# WirelessLamp.net
KiCad netlist of a schematic drawn in Altium Designer
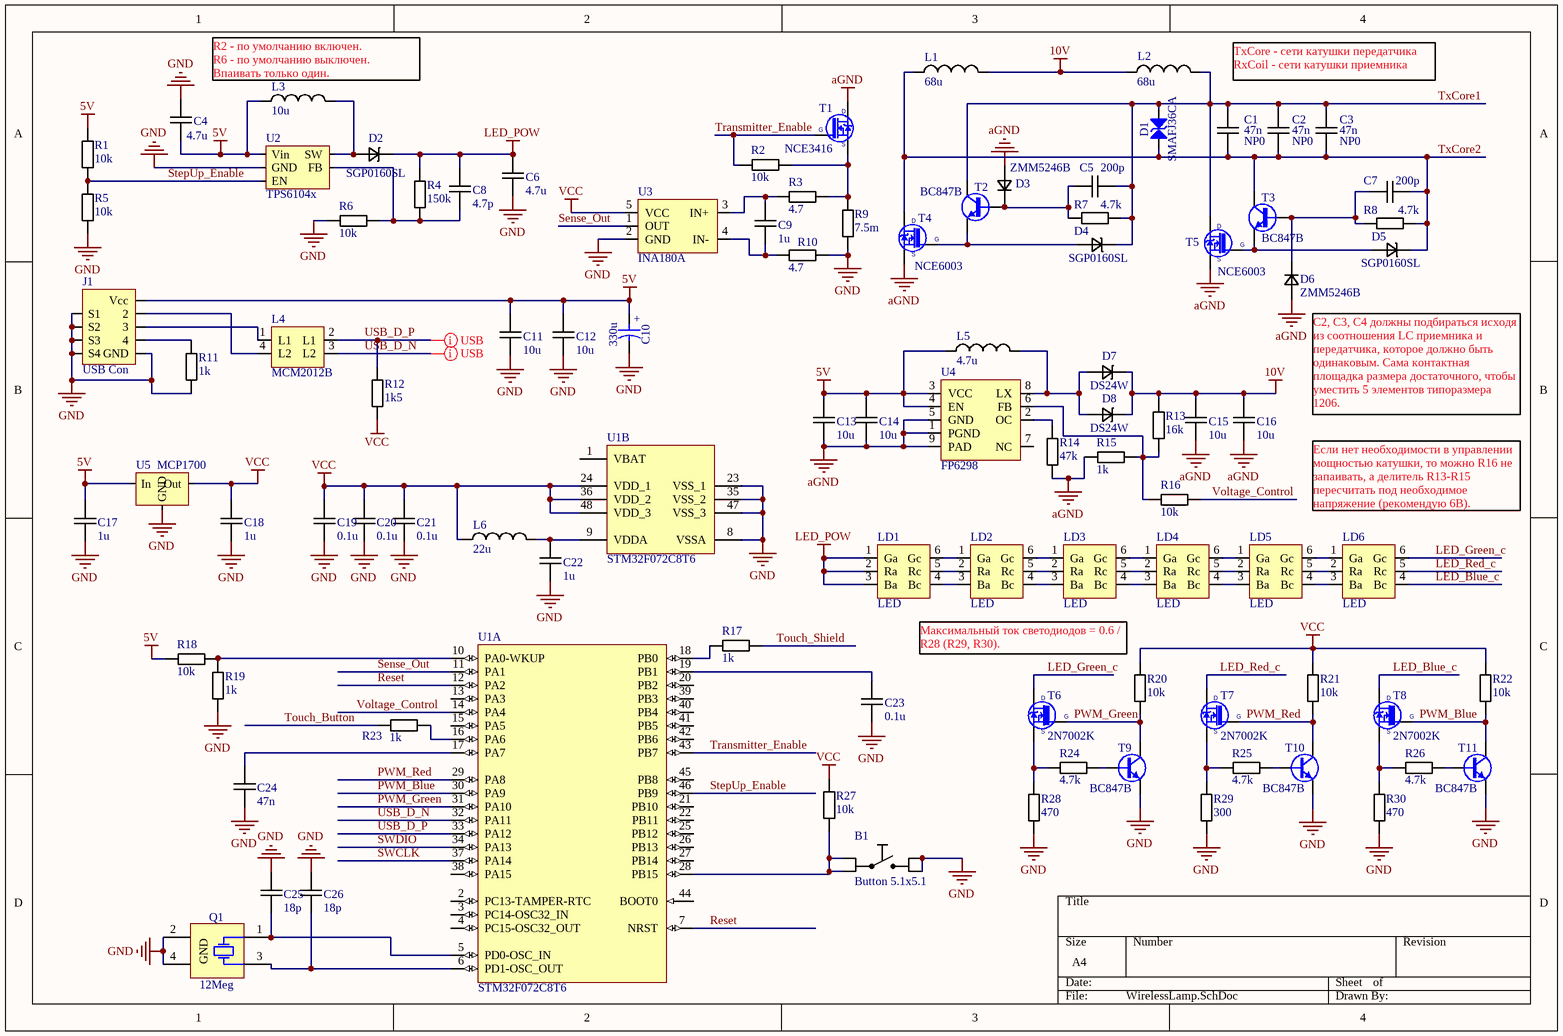
[diagram p0: WirelessLamp.SchDoc]

(export (version "E")
  (design (tool "Eeschema 10.0.6"))
  (components
    (comp (ref "B1")
      (value "Button 5.1x5.1")
      (footprint "TS-1187 combo")
      (fields (field (name "PART") "TS-1187A-B-A-B") (field (name "LCSC PART") "C318884"))
      (libsource (lib "WirelessLamp_lib") (part "Button 5.1x5.1"))
    )
    (comp (ref "C1")
      (value "47n")
      (footprint "CAPC3225L")
      (fields
        (field (name "NAME") "NP0")
        (field (name "PART") "GRM31M5C1H473JA01L")
        (field (name "LCSC PART") "C21812")
        (field (name "VOLTAGE") "50V")
      )
      (libsource (lib "BMFT_lib") (part "Capacitor"))
    )
    (comp (ref "C2")
      (value "47n")
      (footprint "CAPC3225L")
      (fields
        (field (name "NAME") "NP0")
        (field (name "PART") "GRM31M5C1H473JA01L")
        (field (name "LCSC PART") "C21812")
        (field (name "VOLTAGE") "50V")
      )
      (libsource (lib "BMFT_lib") (part "Capacitor"))
    )
    (comp (ref "C3")
      (value "47n")
      (footprint "CAPC3225L")
      (fields
        (field (name "NAME") "NP0")
        (field (name "PART") "GRM31M5C1H473JA01L")
        (field (name "LCSC PART") "C21812")
        (field (name "VOLTAGE") "50V")
      )
      (libsource (lib "BMFT_lib") (part "Capacitor"))
    )
    (comp (ref "C4") (value "4.7u") (footprint "CAPC3216L") (libsource (lib "BMFT_lib") (part "Capacitor")))
    (comp (ref "C5")
      (value "200p")
      (footprint "CAPC2012L")
      (fields (field (name "VOLTAGE") "50V"))
      (libsource (lib "BMFT_lib") (part "Capacitor"))
    )
    (comp (ref "C6")
      (value "4.7u")
      (footprint "CAPC3216L")
      (fields (field (name "VOLTAGE") "50V"))
      (libsource (lib "BMFT_lib") (part "Capacitor"))
    )
    (comp (ref "C7")
      (value "200p")
      (footprint "CAPC2012L")
      (fields (field (name "VOLTAGE") "50V"))
      (libsource (lib "BMFT_lib") (part "Capacitor"))
    )
    (comp (ref "C8") (value "4.7p") (footprint "CAPC1608L") (libsource (lib "BMFT_lib") (part "Capacitor")))
    (comp (ref "C9") (value "1u") (footprint "CAPC1608L") (libsource (lib "BMFT_lib") (part "Capacitor")))
    (comp (ref "C10")
      (value "330u")
      (footprint "CAPPR250-680X1080")
      (description "Polarised capacitor")
      (fields
        (field (name "VOLTAGE") "6.3V")
        (field (name "PART") "6R3AREP331M06X5E20")
        (field (name "AUTHOR") "CERN DEM JLC")
      )
      (libsource (lib "Capacitors") (part "Capacitor - polarized"))
    )
    (comp (ref "C11") (value "10u") (footprint "CAPC3216L") (libsource (lib "BMFT_lib") (part "Capacitor")))
    (comp (ref "C12") (value "10u") (footprint "CAPC3216L") (libsource (lib "BMFT_lib") (part "Capacitor")))
    (comp (ref "C13")
      (value "10u")
      (footprint "CAPC3216L")
      (fields (field (name "VOLTAGE") "16V"))
      (libsource (lib "BMFT_lib") (part "Capacitor"))
    )
    (comp (ref "C14")
      (value "10u")
      (footprint "CAPC3216L")
      (fields (field (name "VOLTAGE") "16V"))
      (libsource (lib "BMFT_lib") (part "Capacitor"))
    )
    (comp (ref "C15")
      (value "10u")
      (footprint "CAPC3225L")
      (fields (field (name "VOLTAGE") "50V"))
      (libsource (lib "BMFT_lib") (part "Capacitor"))
    )
    (comp (ref "C16")
      (value "10u")
      (footprint "CAPC3225L")
      (fields (field (name "VOLTAGE") "50V"))
      (libsource (lib "BMFT_lib") (part "Capacitor"))
    )
    (comp (ref "C17") (value "1u") (footprint "CAPC2012L") (libsource (lib "BMFT_lib") (part "Capacitor")))
    (comp (ref "C18") (value "1u") (footprint "CAPC2012L") (libsource (lib "BMFT_lib") (part "Capacitor")))
    (comp (ref "C19") (value "0.1u") (footprint "CAPC1608L") (libsource (lib "BMFT_lib") (part "Capacitor")))
    (comp (ref "C20") (value "0.1u") (footprint "CAPC1608L") (libsource (lib "BMFT_lib") (part "Capacitor")))
    (comp (ref "C21") (value "0.1u") (footprint "CAPC1608L") (libsource (lib "BMFT_lib") (part "Capacitor")))
    (comp (ref "C22") (value "1u") (footprint "CAPC1608L") (libsource (lib "BMFT_lib") (part "Capacitor")))
    (comp (ref "C23") (value "0.1u") (footprint "CAPC2012L") (libsource (lib "BMFT_lib") (part "Capacitor")))
    (comp (ref "C24") (value "47n") (footprint "CAPC3216L") (libsource (lib "BMFT_lib") (part "Capacitor")))
    (comp (ref "C25") (value "18p") (footprint "CAPC1608L") (libsource (lib "BMFT_lib") (part "Capacitor")))
    (comp (ref "C26") (value "18p") (footprint "CAPC1608L") (libsource (lib "BMFT_lib") (part "Capacitor")))
    (comp (ref "D1")
      (value "SMAFJ36CA")
      (footprint "DIOM5226X262N")
      (description "Transient Voltage Suppressor Diode (Bi-Directional)")
      (fields (field (name "LCSC PART") "C169459") (field (name "AUTHOR") "CERN DEM JLC"))
      (libsource (lib "ICs And Semiconductors") (part "Diode TVS Bi-Directional"))
    )
    (comp (ref "D2")
      (value "SGP0160SL")
      (footprint "SOD-323F")
      (fields (field (name "LCSC PART") "C110413"))
      (libsource (lib "BMFT_lib") (part "Schotky"))
    )
    (comp (ref "D3")
      (value "ZMM5246B")
      (footprint "MELF-D3512-1405")
      (fields (field (name "LCSC PART") "C118699"))
      (libsource (lib "BMFT_lib") (part "Diode_MELF"))
    )
    (comp (ref "D4")
      (value "SGP0160SL")
      (footprint "SOD-323F")
      (fields (field (name "LCSC PART") "C110413"))
      (libsource (lib "BMFT_lib") (part "Schotky"))
    )
    (comp (ref "D5")
      (value "SGP0160SL")
      (footprint "SOD-323F")
      (fields (field (name "LCSC PART") "C110413"))
      (libsource (lib "BMFT_lib") (part "Schotky"))
    )
    (comp (ref "D6")
      (value "ZMM5246B")
      (footprint "MELF-D3512-1405")
      (fields (field (name "LCSC PART") "C118699"))
      (libsource (lib "BMFT_lib") (part "Diode_MELF"))
    )
    (comp (ref "D7")
      (value "DS24W")
      (footprint "SOD123")
      (fields (field (name "LCSC PART") "C108810"))
      (libsource (lib "BMFT_lib") (part "Schotky"))
    )
    (comp (ref "D8")
      (value "DS24W")
      (footprint "SOD123")
      (fields (field (name "LCSC PART") "C108810"))
      (libsource (lib "BMFT_lib") (part "Schotky"))
    )
    (comp (ref "J1") (value "USB Con") (footprint "ZX62D-B-5PA8") (libsource (lib "BMFT_lib") (part "USB")))
    (comp (ref "L1")
      (value "68u")
      (footprint "Ind 8x8")
      (fields (field (name "PART") "SMNR8040-680MT") (field (name "LCSC PART") "C266439"))
      (libsource (lib "WirelessLamp_lib") (part "Inductor"))
    )
    (comp (ref "L2")
      (value "68u")
      (footprint "Ind 8x8")
      (fields (field (name "PART") "SMNR8040-680MT") (field (name "LCSC PART") "C266439"))
      (libsource (lib "WirelessLamp_lib") (part "Inductor"))
    )
    (comp (ref "L3")
      (value "10u")
      (footprint "INDC3225L")
      (fields (field (name "LCSC PART") "C329581") (field (name "PART") "MRSC252A10-100M-N"))
      (libsource (lib "BMFT_lib") (part "Inductor"))
    )
    (comp (ref "L4")
      (value "MCM2012B")
      (footprint "MCM2012B")
      (fields (field (name "PART") "MCM2012B900GBE") (field (name "LCSC PART") "C315725"))
      (libsource (lib "WirelessLamp_lib") (part "MCM2012B"))
    )
    (comp (ref "L5")
      (value "4.7u")
      (footprint "Ind 8x8")
      (fields (field (name "PART") "SMNR8040-4R7MT") (field (name "LCSC PART") "C266436"))
      (libsource (lib "WirelessLamp_lib") (part "Inductor"))
    )
    (comp (ref "L6") (value "22u") (footprint "INDC2012L") (libsource (lib "BMFT_lib") (part "Inductor")))
    (comp (ref "LD1")
      (value "LED")
      (footprint "LED5060")
      (fields (field (name "PART") "HL-AF-5060H271BU46FU79GC-S1-THL") (field (name "LCSC PART") "C219409"))
      (libsource (lib "WirelessLamp_lib") (part "RGB LED 5060"))
    )
    (comp (ref "LD2")
      (value "LED")
      (footprint "LED5060")
      (fields (field (name "PART") "HL-AF-5060H271BU46FU79GC-S1-THL") (field (name "LCSC PART") "C219409"))
      (libsource (lib "WirelessLamp_lib") (part "RGB LED 5060"))
    )
    (comp (ref "LD3")
      (value "LED")
      (footprint "LED5060")
      (fields (field (name "PART") "HL-AF-5060H271BU46FU79GC-S1-THL") (field (name "LCSC PART") "C219409"))
      (libsource (lib "WirelessLamp_lib") (part "RGB LED 5060"))
    )
    (comp (ref "LD4")
      (value "LED")
      (footprint "LED5060")
      (fields (field (name "PART") "HL-AF-5060H271BU46FU79GC-S1-THL") (field (name "LCSC PART") "C219409"))
      (libsource (lib "WirelessLamp_lib") (part "RGB LED 5060"))
    )
    (comp (ref "LD5")
      (value "LED")
      (footprint "LED5060")
      (fields (field (name "PART") "HL-AF-5060H271BU46FU79GC-S1-THL") (field (name "LCSC PART") "C219409"))
      (libsource (lib "WirelessLamp_lib") (part "RGB LED 5060"))
    )
    (comp (ref "LD6")
      (value "LED")
      (footprint "LED5060")
      (fields (field (name "PART") "HL-AF-5060H271BU46FU79GC-S1-THL") (field (name "LCSC PART") "C219409"))
      (libsource (lib "WirelessLamp_lib") (part "RGB LED 5060"))
    )
    (comp (ref "Q1")
      (value "12Meg")
      (footprint "XTAL_ABRACON_ABM8-166")
      (description "Crystal 4 pins 1=XTAL Control 2=GND3=XTAL 4=GND")
      (fields
        (field (name "PART") "7U12000E12UCG")
        (field (name "LCSC PART") "C251605")
        (field (name "AUTHOR") "CERN DEM MR")
      )
      (libsource (lib "ICs And Semiconductors") (part "Quartz Crystal 1X 2GND 3X 4GND"))
    )
    (comp (ref "R1") (value "10k") (footprint "RESC1608L") (libsource (lib "BMFT_lib") (part "Resistor")))
    (comp (ref "R2") (value "10k") (footprint "RESC1608L") (libsource (lib "BMFT_lib") (part "Resistor")))
    (comp (ref "R3") (value "4.7") (footprint "RESC1608L") (libsource (lib "BMFT_lib") (part "Resistor")))
    (comp (ref "R4") (value "150k") (footprint "RESC1608L") (libsource (lib "BMFT_lib") (part "Resistor")))
    (comp (ref "R5") (value "10k") (footprint "RESC1608L") (libsource (lib "BMFT_lib") (part "Resistor")))
    (comp (ref "R6") (value "10k") (footprint "RESC1608L") (libsource (lib "BMFT_lib") (part "Resistor")))
    (comp (ref "R7") (value "4.7k") (footprint "RESC2012L") (libsource (lib "BMFT_lib") (part "Resistor")))
    (comp (ref "R8") (value "4.7k") (footprint "RESC2012L") (libsource (lib "BMFT_lib") (part "Resistor")))
    (comp (ref "R9")
      (value "7.5m")
      (footprint "RESC2012M")
      (fields (field (name "LCSC PART") "C156368"))
      (libsource (lib "BMFT_lib") (part "Resistor"))
    )
    (comp (ref "R10") (value "4.7") (footprint "RESC1608L") (libsource (lib "BMFT_lib") (part "Resistor")))
    (comp (ref "R11") (value "1k") (footprint "RESC1608L") (libsource (lib "BMFT_lib") (part "Resistor")))
    (comp (ref "R12") (value "1k5") (footprint "RESC1608L") (libsource (lib "BMFT_lib") (part "Resistor")))
    (comp (ref "R13") (value "16k") (footprint "RESC1608L") (libsource (lib "BMFT_lib") (part "Resistor")))
    (comp (ref "R14") (value "47k") (footprint "RESC1608L") (libsource (lib "BMFT_lib") (part "Resistor")))
    (comp (ref "R15") (value "1k") (footprint "RESC1608L") (libsource (lib "BMFT_lib") (part "Resistor")))
    (comp (ref "R16") (value "10k") (footprint "RESC1608L") (libsource (lib "BMFT_lib") (part "Resistor")))
    (comp (ref "R17") (value "1k") (footprint "RESC1608L") (libsource (lib "BMFT_lib") (part "Resistor")))
    (comp (ref "R18") (value "10k") (footprint "RESC1608L") (libsource (lib "BMFT_lib") (part "Resistor")))
    (comp (ref "R19") (value "1k") (footprint "RESC1608L") (libsource (lib "BMFT_lib") (part "Resistor")))
    (comp (ref "R20") (value "10k") (footprint "RESC1608L") (libsource (lib "BMFT_lib") (part "Resistor")))
    (comp (ref "R21") (value "10k") (footprint "RESC1608L") (libsource (lib "BMFT_lib") (part "Resistor")))
    (comp (ref "R22") (value "10k") (footprint "RESC1608L") (libsource (lib "BMFT_lib") (part "Resistor")))
    (comp (ref "R23") (value "1k") (footprint "RESC1608L") (libsource (lib "BMFT_lib") (part "Resistor")))
    (comp (ref "R24") (value "4.7k") (footprint "RESC1608L") (libsource (lib "BMFT_lib") (part "Resistor")))
    (comp (ref "R25") (value "4.7k") (footprint "RESC1608L") (libsource (lib "BMFT_lib") (part "Resistor")))
    (comp (ref "R26") (value "4.7k") (footprint "RESC1608L") (libsource (lib "BMFT_lib") (part "Resistor")))
    (comp (ref "R27") (value "10k") (footprint "RESC1608L") (libsource (lib "BMFT_lib") (part "Resistor")))
    (comp (ref "R28") (value "470") (footprint "RESC2012L") (libsource (lib "BMFT_lib") (part "Resistor")))
    (comp (ref "R29") (value "300") (footprint "RESC2012L") (libsource (lib "BMFT_lib") (part "Resistor")))
    (comp (ref "R30") (value "470") (footprint "RESC2012L") (libsource (lib "BMFT_lib") (part "Resistor")))
    (comp (ref "T1")
      (value "NCE3416")
      (footprint "SOT95P237X112-3N")
      (description "N-CHANNEL MOSFET WITH ZENER DIODE")
      (fields (field (name "LCSC PART") "C113491") (field (name "AUTHOR") "CERN DEM JMW"))
      (libsource (lib "") (part "N-MOSFET-DZ 1G 2S 3D_1"))
    )
    (comp (ref "T2")
      (value "BC847B")
      (footprint "SOT95P230X110-3N")
      (description "NPN Transistor")
      (fields (field (name "AUTHOR") "CERN DEM JLC"))
      (libsource (lib "ICs And Semiconductors") (part "NPN B1 E2 C3"))
    )
    (comp (ref "T3")
      (value "BC847B")
      (footprint "SOT95P230X110-3N")
      (description "NPN Transistor")
      (fields (field (name "AUTHOR") "CERN DEM JLC"))
      (libsource (lib "") (part "NPN B1 E2 C3_1"))
    )
    (comp (ref "T4")
      (value "NCE6003")
      (footprint "SOT95P237X112-3N")
      (description "N-CHANNEL MOSFET WITH ZENER DIODE")
      (fields (field (name "LCSC PART") "C112351") (field (name "AUTHOR") "CERN DEM JMW"))
      (libsource (lib "ICs And Semiconductors") (part "N-MOSFET-DZ 1G 2S 3D"))
    )
    (comp (ref "T5")
      (value "NCE6003")
      (footprint "SOT95P237X112-3N")
      (description "N-CHANNEL MOSFET WITH ZENER DIODE")
      (fields (field (name "LCSC PART") "C112351") (field (name "AUTHOR") "CERN DEM JMW"))
      (libsource (lib "ICs And Semiconductors") (part "N-MOSFET-DZ 1G 2S 3D"))
    )
    (comp (ref "T6")
      (value "2N7002K")
      (footprint "SOT95P237X112-3N")
      (description "N-CHANNEL MOSFET WITH ZENER DIODE")
      (fields (field (name "LCSC PART") "C38161") (field (name "AUTHOR") "CERN DEM JMW"))
      (libsource (lib "ICs And Semiconductors") (part "N-MOSFET-DZ 1G 2S 3D"))
    )
    (comp (ref "T7")
      (value "2N7002K")
      (footprint "SOT95P237X112-3N")
      (description "N-CHANNEL MOSFET WITH ZENER DIODE")
      (fields (field (name "LCSC PART") "C38161") (field (name "AUTHOR") "CERN DEM JMW"))
      (libsource (lib "ICs And Semiconductors") (part "N-MOSFET-DZ 1G 2S 3D"))
    )
    (comp (ref "T8")
      (value "2N7002K")
      (footprint "SOT95P237X112-3N")
      (description "N-CHANNEL MOSFET WITH ZENER DIODE")
      (fields (field (name "LCSC PART") "C38161") (field (name "AUTHOR") "CERN DEM JMW"))
      (libsource (lib "ICs And Semiconductors") (part "N-MOSFET-DZ 1G 2S 3D"))
    )
    (comp (ref "T9")
      (value "BC847B")
      (footprint "SOT95P230X110-3N")
      (description "NPN Transistor")
      (fields (field (name "AUTHOR") "CERN DEM JLC"))
      (libsource (lib "ICs And Semiconductors") (part "NPN B1 E2 C3"))
    )
    (comp (ref "T10")
      (value "BC847B")
      (footprint "SOT95P230X110-3N")
      (description "NPN Transistor")
      (fields (field (name "AUTHOR") "CERN DEM JLC"))
      (libsource (lib "ICs And Semiconductors") (part "NPN B1 E2 C3"))
    )
    (comp (ref "T11")
      (value "BC847B")
      (footprint "SOT95P230X110-3N")
      (description "NPN Transistor")
      (fields (field (name "AUTHOR") "CERN DEM JLC"))
      (libsource (lib "ICs And Semiconductors") (part "NPN B1 E2 C3"))
    )
    (comp (ref "U1")
      (value "STM32F072C8T6")
      (footprint "STM-LQFP48_N")
      (fields (field (name "LCSC PART") "C80488"))
      (libsource (lib "STMicroelectronics STM32 F1") (part "STM32F103C8T6"))
    )
    (comp (ref "U2")
      (value "TPS6104x")
      (footprint "SOT23-5AL")
      (fields (field (name "PART") "TPS61041DBVR") (field (name "LCSC PART") "C9846"))
      (libsource (lib "BMFT_lib") (part "TPS6104x"))
    )
    (comp (ref "U3")
      (value "INA180A")
      (footprint "SOT23-5AN")
      (fields (field (name "LCSC PART") "C188337") (field (name "PART") "INA180A4IDBVR"))
      (libsource (lib "WirelessLamp_lib") (part "INA180A"))
    )
    (comp (ref "U4")
      (value "FP6298")
      (footprint "SOIC127P600-8DL")
      (fields (field (name "PART") "FP6298XR-G1") (field (name "LCSC PART") "C88319"))
      (libsource (lib "WirelessLamp_lib") (part "FP6298"))
    )
    (comp (ref "U5")
      (value "MCP1700")
      (footprint "SOT23-3L")
      (fields (field (name "PART") "RS3219-3.3YF3") (field (name "LCSC PART") "C255487"))
      (libsource (lib "BMFT_lib") (part "MCP1700"))
    )
  )
  (nets
    (net (code "1") (name "/LED_Blue_c") (class "Default")
      (node (ref "LD6") (pin "4") (pinfunction "Bc_4") (pintype "passive"))
      (node (ref "T8") (pin "3") (pinfunction "D_3") (pintype "passive"))
    )
    (net (code "2") (name "/LED_Green_c") (class "Default")
      (node (ref "LD6") (pin "6") (pinfunction "Gc_6") (pintype "passive"))
      (node (ref "T6") (pin "3") (pinfunction "D_3") (pintype "passive"))
    )
    (net (code "3") (name "/LED_Red_c") (class "Default")
      (node (ref "LD6") (pin "5") (pinfunction "Rc_5") (pintype "passive"))
      (node (ref "T7") (pin "3") (pinfunction "D_3") (pintype "passive"))
    )
    (net (code "4") (name "/PWM_Blue") (class "Default")
      (node (ref "R22") (pin "1") (pintype "passive"))
      (node (ref "T11") (pin "3") (pinfunction "C_3") (pintype "passive"))
      (node (ref "T8") (pin "1") (pinfunction "G_1") (pintype "passive"))
      (node (ref "U1") (pin "30") (pinfunction "PA9_30") (pintype "bidirectional"))
    )
    (net (code "5") (name "/PWM_Green") (class "Default")
      (node (ref "R20") (pin "1") (pintype "passive"))
      (node (ref "T6") (pin "1") (pinfunction "G_1") (pintype "passive"))
      (node (ref "T9") (pin "3") (pinfunction "C_3") (pintype "passive"))
      (node (ref "U1") (pin "31") (pinfunction "PA10_31") (pintype "bidirectional"))
    )
    (net (code "6") (name "/PWM_Red") (class "Default")
      (node (ref "R21") (pin "1") (pintype "passive"))
      (node (ref "T10") (pin "3") (pinfunction "C_3") (pintype "passive"))
      (node (ref "T7") (pin "1") (pinfunction "G_1") (pintype "passive"))
      (node (ref "U1") (pin "29") (pinfunction "PA8_29") (pintype "bidirectional"))
    )
    (net (code "7") (name "/Reset") (class "Default")
      (node (ref "U1") (pin "12") (pinfunction "PA2_12") (pintype "bidirectional"))
      (node (ref "U1") (pin "7") (pinfunction "NRST_7") (pintype "bidirectional"))
    )
    (net (code "8") (name "/SWCLK") (class "Default")
      (node (ref "U1") (pin "37") (pinfunction "PA14_37") (pintype "bidirectional"))
    )
    (net (code "9") (name "/SWDIO") (class "Default")
      (node (ref "U1") (pin "34") (pinfunction "PA13_34") (pintype "bidirectional"))
    )
    (net (code "10") (name "/Sense_Out") (class "Default")
      (node (ref "U1") (pin "11") (pinfunction "PA1_11") (pintype "bidirectional"))
      (node (ref "U3") (pin "1") (pinfunction "OUT_1") (pintype "passive"))
    )
    (net (code "11") (name "/StepUp_Enable") (class "Default")
      (node (ref "R1") (pin "1") (pintype "passive"))
      (node (ref "R5") (pin "2") (pintype "passive"))
      (node (ref "U1") (pin "46") (pinfunction "PB9_46") (pintype "bidirectional"))
      (node (ref "U2") (pin "4") (pinfunction "EN_4") (pintype "passive"))
    )
    (net (code "12") (name "/Touch_Button") (class "Default")
      (node (ref "R23") (pin "1") (pintype "passive"))
    )
    (net (code "13") (name "/Touch_Shield") (class "Default")
      (node (ref "R17") (pin "2") (pintype "passive"))
    )
    (net (code "14") (name "/Transmitter_Enable") (class "Default")
      (node (ref "R2") (pin "1") (pintype "passive"))
      (node (ref "T1") (pin "1") (pinfunction "G_1") (pintype "passive"))
      (node (ref "U1") (pin "43") (pinfunction "PB7_43") (pintype "bidirectional"))
    )
    (net (code "15") (name "/TxCore1") (class "Default")
      (node (ref "C1") (pin "2") (pintype "passive"))
      (node (ref "C2") (pin "2") (pintype "passive"))
      (node (ref "C3") (pin "2") (pintype "passive"))
      (node (ref "C5") (pin "1") (pintype "passive"))
      (node (ref "D1") (pin "1") (pinfunction "C_1") (pintype "passive"))
      (node (ref "D4") (pin "2") (pintype "passive"))
      (node (ref "L2") (pin "2") (pintype "passive"))
      (node (ref "R7") (pin "1") (pintype "passive"))
      (node (ref "T2") (pin "3") (pinfunction "C_3") (pintype "passive"))
      (node (ref "T5") (pin "3") (pinfunction "D_3") (pintype "passive"))
    )
    (net (code "16") (name "/TxCore2") (class "Default")
      (node (ref "C1") (pin "1") (pintype "passive"))
      (node (ref "C2") (pin "1") (pintype "passive"))
      (node (ref "C3") (pin "1") (pintype "passive"))
      (node (ref "C7") (pin "1") (pintype "passive"))
      (node (ref "D1") (pin "2") (pinfunction "A_2") (pintype "passive"))
      (node (ref "D5") (pin "2") (pintype "passive"))
      (node (ref "L1") (pin "1") (pintype "passive"))
      (node (ref "R8") (pin "1") (pintype "passive"))
      (node (ref "T3") (pin "3") (pinfunction "C_3") (pintype "passive"))
      (node (ref "T4") (pin "3") (pinfunction "D_3") (pintype "passive"))
    )
    (net (code "17") (name "/USB_D_N") (class "Default")
      (node (ref "L4") (pin "3") (pinfunction "L2_3") (pintype "passive"))
      (node (ref "U1") (pin "32") (pinfunction "PA11_32") (pintype "bidirectional"))
    )
    (net (code "18") (name "/USB_D_P") (class "Default")
      (node (ref "L4") (pin "2") (pinfunction "L1_2") (pintype "passive"))
      (node (ref "R12") (pin "2") (pintype "passive"))
      (node (ref "U1") (pin "33") (pinfunction "PA12_33") (pintype "bidirectional"))
    )
    (net (code "19") (name "/Voltage_Control") (class "Default")
      (node (ref "R16") (pin "2") (pintype "passive"))
      (node (ref "U1") (pin "14") (pinfunction "PA4_14") (pintype "bidirectional"))
    )
    (net (code "20") (name "5V") (class "Default")
      (node (ref "C10") (pin "1") (pinfunction "1_1") (pintype "passive"))
      (node (ref "C11") (pin "2") (pintype "passive"))
      (node (ref "C12") (pin "2") (pintype "passive"))
      (node (ref "C13") (pin "2") (pintype "passive"))
      (node (ref "C14") (pin "2") (pintype "passive"))
      (node (ref "C17") (pin "2") (pintype "passive"))
      (node (ref "C4") (pin "1") (pintype "passive"))
      (node (ref "J1") (pin "1") (pinfunction "Vcc_1") (pintype "power_in"))
      (node (ref "L3") (pin "1") (pintype "passive"))
      (node (ref "L5") (pin "1") (pintype "passive"))
      (node (ref "R1") (pin "2") (pintype "passive"))
      (node (ref "R18") (pin "2") (pintype "passive"))
      (node (ref "U2") (pin "5") (pinfunction "Vin_5") (pintype "power_in"))
      (node (ref "U4") (pin "3") (pinfunction "VCC_3") (pintype "power_in"))
      (node (ref "U4") (pin "4") (pinfunction "EN_4") (pintype "passive"))
      (node (ref "U5") (pin "3") (pinfunction "In_3") (pintype "passive"))
    )
    (net (code "21") (name "10V") (class "Default")
      (node (ref "C15") (pin "2") (pintype "passive"))
      (node (ref "C16") (pin "2") (pintype "passive"))
      (node (ref "D7") (pin "2") (pintype "passive"))
      (node (ref "D8") (pin "2") (pintype "passive"))
      (node (ref "L1") (pin "2") (pintype "passive"))
      (node (ref "L2") (pin "1") (pintype "passive"))
      (node (ref "R13") (pin "2") (pintype "passive"))
    )
    (net (code "22") (name "GND") (class "Default")
      (node (ref "B1") (pin "3") (pinfunction "FB_3") (pintype "passive"))
      (node (ref "B1") (pin "4") (pinfunction "FB_4") (pintype "passive"))
      (node (ref "C10") (pin "2") (pinfunction "2_2") (pintype "passive"))
      (node (ref "C11") (pin "1") (pintype "passive"))
      (node (ref "C12") (pin "1") (pintype "passive"))
      (node (ref "C17") (pin "1") (pintype "passive"))
      (node (ref "C18") (pin "1") (pintype "passive"))
      (node (ref "C19") (pin "1") (pintype "passive"))
      (node (ref "C20") (pin "1") (pintype "passive"))
      (node (ref "C21") (pin "1") (pintype "passive"))
      (node (ref "C22") (pin "1") (pintype "passive"))
      (node (ref "C23") (pin "1") (pintype "passive"))
      (node (ref "C24") (pin "1") (pintype "passive"))
      (node (ref "C25") (pin "2") (pintype "passive"))
      (node (ref "C26") (pin "2") (pintype "passive"))
      (node (ref "C4") (pin "2") (pintype "passive"))
      (node (ref "C6") (pin "1") (pintype "passive"))
      (node (ref "J1") (pin "5") (pinfunction "GND_5") (pintype "power_in"))
      (node (ref "J1") (pin "S1") (pinfunction "S1_S1") (pintype "passive"))
      (node (ref "J1") (pin "S2") (pinfunction "S2_S2") (pintype "passive"))
      (node (ref "J1") (pin "S3") (pinfunction "S3_S3") (pintype "passive"))
      (node (ref "J1") (pin "S4") (pinfunction "S4_S4") (pintype "passive"))
      (node (ref "Q1") (pin "2") (pinfunction "GND_2") (pintype "power_in"))
      (node (ref "Q1") (pin "4") (pinfunction "GND_4") (pintype "power_in"))
      (node (ref "R10") (pin "2") (pintype "passive"))
      (node (ref "R11") (pin "2") (pintype "passive"))
      (node (ref "R19") (pin "1") (pintype "passive"))
      (node (ref "R28") (pin "2") (pintype "passive"))
      (node (ref "R29") (pin "1") (pintype "passive"))
      (node (ref "R30") (pin "1") (pintype "passive"))
      (node (ref "R5") (pin "1") (pintype "passive"))
      (node (ref "R6") (pin "1") (pintype "passive"))
      (node (ref "R9") (pin "1") (pintype "passive"))
      (node (ref "T10") (pin "2") (pinfunction "E_2") (pintype "passive"))
      (node (ref "T11") (pin "2") (pinfunction "E_2") (pintype "passive"))
      (node (ref "T9") (pin "2") (pinfunction "E_2") (pintype "passive"))
      (node (ref "U1") (pin "23") (pinfunction "VSS_1_23") (pintype "power_in"))
      (node (ref "U1") (pin "35") (pinfunction "VSS_2_35") (pintype "power_in"))
      (node (ref "U1") (pin "47") (pinfunction "VSS_3_47") (pintype "power_in"))
      (node (ref "U1") (pin "8") (pinfunction "VSSA_8") (pintype "power_in"))
      (node (ref "U2") (pin "2") (pinfunction "GND_2") (pintype "power_in"))
      (node (ref "U3") (pin "2") (pinfunction "GND_2") (pintype "passive"))
      (node (ref "U5") (pin "1") (pinfunction "GND_1") (pintype "passive"))
    )
    (net (code "23") (name "LED_POW") (class "Default")
      (node (ref "C6") (pin "2") (pintype "passive"))
      (node (ref "C8") (pin "2") (pintype "passive"))
      (node (ref "D2") (pin "2") (pintype "passive"))
      (node (ref "LD1") (pin "1") (pinfunction "Ga_1") (pintype "passive"))
      (node (ref "LD1") (pin "2") (pinfunction "Ra_2") (pintype "passive"))
      (node (ref "LD1") (pin "3") (pinfunction "Ba_3") (pintype "passive"))
      (node (ref "R4") (pin "2") (pintype "passive"))
    )
    (net (code "24") (name "Net-(J1-Pad2)") (class "Default")
      (node (ref "J1") (pin "2") (pinfunction "2_2") (pintype "passive"))
      (node (ref "L4") (pin "4") (pinfunction "L2_4") (pintype "passive"))
    )
    (net (code "25") (name "Net-(J1-Pad3)") (class "Default")
      (node (ref "J1") (pin "3") (pinfunction "3_3") (pintype "passive"))
      (node (ref "L4") (pin "1") (pinfunction "L1_1") (pintype "passive"))
    )
    (net (code "26") (name "Net-(J1-Pad4)") (class "Default")
      (node (ref "J1") (pin "4") (pinfunction "4_4") (pintype "passive"))
      (node (ref "R11") (pin "1") (pintype "passive"))
    )
    (net (code "27") (name "Net-(LD1-Bc)") (class "Default")
      (node (ref "LD1") (pin "4") (pinfunction "Bc_4") (pintype "passive"))
      (node (ref "LD2") (pin "3") (pinfunction "Ba_3") (pintype "passive"))
    )
    (net (code "28") (name "Net-(LD1-Gc)") (class "Default")
      (node (ref "LD1") (pin "6") (pinfunction "Gc_6") (pintype "passive"))
      (node (ref "LD2") (pin "1") (pinfunction "Ga_1") (pintype "passive"))
    )
    (net (code "29") (name "Net-(LD1-Rc)") (class "Default")
      (node (ref "LD1") (pin "5") (pinfunction "Rc_5") (pintype "passive"))
      (node (ref "LD2") (pin "2") (pinfunction "Ra_2") (pintype "passive"))
    )
    (net (code "30") (name "Net-(LD2-Bc)") (class "Default")
      (node (ref "LD2") (pin "4") (pinfunction "Bc_4") (pintype "passive"))
      (node (ref "LD3") (pin "3") (pinfunction "Ba_3") (pintype "passive"))
    )
    (net (code "31") (name "Net-(LD2-Gc)") (class "Default")
      (node (ref "LD2") (pin "6") (pinfunction "Gc_6") (pintype "passive"))
      (node (ref "LD3") (pin "1") (pinfunction "Ga_1") (pintype "passive"))
    )
    (net (code "32") (name "Net-(LD2-Rc)") (class "Default")
      (node (ref "LD2") (pin "5") (pinfunction "Rc_5") (pintype "passive"))
      (node (ref "LD3") (pin "2") (pinfunction "Ra_2") (pintype "passive"))
    )
    (net (code "33") (name "Net-(LD3-Bc)") (class "Default")
      (node (ref "LD3") (pin "4") (pinfunction "Bc_4") (pintype "passive"))
      (node (ref "LD4") (pin "3") (pinfunction "Ba_3") (pintype "passive"))
    )
    (net (code "34") (name "Net-(LD3-Gc)") (class "Default")
      (node (ref "LD3") (pin "6") (pinfunction "Gc_6") (pintype "passive"))
      (node (ref "LD4") (pin "1") (pinfunction "Ga_1") (pintype "passive"))
    )
    (net (code "35") (name "Net-(LD3-Rc)") (class "Default")
      (node (ref "LD3") (pin "5") (pinfunction "Rc_5") (pintype "passive"))
      (node (ref "LD4") (pin "2") (pinfunction "Ra_2") (pintype "passive"))
    )
    (net (code "36") (name "Net-(LD4-Bc)") (class "Default")
      (node (ref "LD4") (pin "4") (pinfunction "Bc_4") (pintype "passive"))
      (node (ref "LD5") (pin "3") (pinfunction "Ba_3") (pintype "passive"))
    )
    (net (code "37") (name "Net-(LD4-Gc)") (class "Default")
      (node (ref "LD4") (pin "6") (pinfunction "Gc_6") (pintype "passive"))
      (node (ref "LD5") (pin "1") (pinfunction "Ga_1") (pintype "passive"))
    )
    (net (code "38") (name "Net-(LD4-Rc)") (class "Default")
      (node (ref "LD4") (pin "5") (pinfunction "Rc_5") (pintype "passive"))
      (node (ref "LD5") (pin "2") (pinfunction "Ra_2") (pintype "passive"))
    )
    (net (code "39") (name "Net-(LD5-Bc)") (class "Default")
      (node (ref "LD5") (pin "4") (pinfunction "Bc_4") (pintype "passive"))
      (node (ref "LD6") (pin "3") (pinfunction "Ba_3") (pintype "passive"))
    )
    (net (code "40") (name "Net-(LD5-Gc)") (class "Default")
      (node (ref "LD5") (pin "6") (pinfunction "Gc_6") (pintype "passive"))
      (node (ref "LD6") (pin "1") (pinfunction "Ga_1") (pintype "passive"))
    )
    (net (code "41") (name "Net-(LD5-Rc)") (class "Default")
      (node (ref "LD5") (pin "5") (pinfunction "Rc_5") (pintype "passive"))
      (node (ref "LD6") (pin "2") (pinfunction "Ra_2") (pintype "passive"))
    )
    (net (code "42") (name "Net-(T1-S)") (class "Default")
      (node (ref "R2") (pin "2") (pintype "passive"))
      (node (ref "R3") (pin "2") (pintype "passive"))
      (node (ref "R9") (pin "2") (pintype "passive"))
      (node (ref "T1") (pin "2") (pinfunction "S_2") (pintype "passive"))
    )
    (net (code "43") (name "Net-(T2-B)") (class "Default")
      (node (ref "C5") (pin "2") (pintype "passive"))
      (node (ref "D3") (pin "2") (pintype "passive"))
      (node (ref "R7") (pin "2") (pintype "passive"))
      (node (ref "T2") (pin "1") (pinfunction "B_1") (pintype "passive"))
    )
    (net (code "44") (name "Net-(T2-E)") (class "Default")
      (node (ref "D4") (pin "1") (pintype "passive"))
      (node (ref "T2") (pin "2") (pinfunction "E_2") (pintype "passive"))
      (node (ref "T4") (pin "1") (pinfunction "G_1") (pintype "passive"))
    )
    (net (code "45") (name "Net-(T3-B)") (class "Default")
      (node (ref "C7") (pin "2") (pintype "passive"))
      (node (ref "D6") (pin "2") (pintype "passive"))
      (node (ref "R8") (pin "2") (pintype "passive"))
      (node (ref "T3") (pin "1") (pinfunction "B_1") (pintype "passive"))
    )
    (net (code "46") (name "Net-(T3-E)") (class "Default")
      (node (ref "D5") (pin "1") (pintype "passive"))
      (node (ref "T3") (pin "2") (pinfunction "E_2") (pintype "passive"))
      (node (ref "T5") (pin "1") (pinfunction "G_1") (pintype "passive"))
    )
    (net (code "47") (name "Net-(T6-S)") (class "Default")
      (node (ref "R24") (pin "1") (pintype "passive"))
      (node (ref "R28") (pin "1") (pintype "passive"))
      (node (ref "T6") (pin "2") (pinfunction "S_2") (pintype "passive"))
    )
    (net (code "48") (name "Net-(T7-S)") (class "Default")
      (node (ref "R25") (pin "1") (pintype "passive"))
      (node (ref "R29") (pin "2") (pintype "passive"))
      (node (ref "T7") (pin "2") (pinfunction "S_2") (pintype "passive"))
    )
    (net (code "49") (name "Net-(T8-S)") (class "Default")
      (node (ref "R26") (pin "1") (pintype "passive"))
      (node (ref "R30") (pin "2") (pintype "passive"))
      (node (ref "T8") (pin "2") (pinfunction "S_2") (pintype "passive"))
    )
    (net (code "50") (name "Net-(T9-B)") (class "Default")
      (node (ref "R24") (pin "2") (pintype "passive"))
      (node (ref "T9") (pin "1") (pinfunction "B_1") (pintype "passive"))
    )
    (net (code "51") (name "Net-(T10-B)") (class "Default")
      (node (ref "R25") (pin "2") (pintype "passive"))
      (node (ref "T10") (pin "1") (pinfunction "B_1") (pintype "passive"))
    )
    (net (code "52") (name "Net-(T11-B)") (class "Default")
      (node (ref "R26") (pin "2") (pintype "passive"))
      (node (ref "T11") (pin "1") (pinfunction "B_1") (pintype "passive"))
    )
    (net (code "53") (name "Net-(U1A-PA0-WKUP)") (class "Default")
      (node (ref "R18") (pin "1") (pintype "passive"))
      (node (ref "R19") (pin "2") (pintype "passive"))
      (node (ref "U1") (pin "10") (pinfunction "PA0-WKUP_10") (pintype "bidirectional"))
    )
    (net (code "54") (name "Net-(U1A-PA6)") (class "Default")
      (node (ref "R23") (pin "2") (pintype "passive"))
      (node (ref "U1") (pin "16") (pinfunction "PA6_16") (pintype "bidirectional"))
    )
    (net (code "55") (name "Net-(U1A-PA7)") (class "Default")
      (node (ref "C24") (pin "2") (pintype "passive"))
      (node (ref "U1") (pin "17") (pinfunction "PA7_17") (pintype "bidirectional"))
    )
    (net (code "56") (name "Net-(U1A-PB0)") (class "Default")
      (node (ref "R17") (pin "1") (pintype "passive"))
      (node (ref "U1") (pin "18") (pinfunction "PB0_18") (pintype "bidirectional"))
    )
    (net (code "57") (name "Net-(U1A-PB1)") (class "Default")
      (node (ref "C23") (pin "2") (pintype "passive"))
      (node (ref "U1") (pin "19") (pinfunction "PB1_19") (pintype "bidirectional"))
    )
    (net (code "58") (name "Net-(U1A-PB15)") (class "Default")
      (node (ref "B1") (pin "1") (pinfunction "FB_1") (pintype "passive"))
      (node (ref "B1") (pin "2") (pinfunction "FB_2") (pintype "passive"))
      (node (ref "R27") (pin "1") (pintype "passive"))
      (node (ref "U1") (pin "28") (pinfunction "PB15_28") (pintype "bidirectional"))
    )
    (net (code "59") (name "Net-(U1A-PD0-OSC_IN)") (class "Default")
      (node (ref "C25") (pin "1") (pintype "passive"))
      (node (ref "Q1") (pin "1") (pinfunction "X_1") (pintype "passive"))
      (node (ref "U1") (pin "5") (pinfunction "PD0-OSC_IN_5") (pintype "bidirectional"))
    )
    (net (code "60") (name "Net-(U1A-PD1-OSC_OUT)") (class "Default")
      (node (ref "C26") (pin "1") (pintype "passive"))
      (node (ref "Q1") (pin "3") (pinfunction "X_3") (pintype "passive"))
      (node (ref "U1") (pin "6") (pinfunction "PD1-OSC_OUT_6") (pintype "bidirectional"))
    )
    (net (code "61") (name "Net-(U1B-VDDA)") (class "Default")
      (node (ref "C22") (pin "2") (pintype "passive"))
      (node (ref "L6") (pin "2") (pintype "passive"))
      (node (ref "U1") (pin "9") (pinfunction "VDDA_9") (pintype "power_in"))
    )
    (net (code "62") (name "Net-(U2-FB)") (class "Default")
      (node (ref "C8") (pin "1") (pintype "passive"))
      (node (ref "R4") (pin "1") (pintype "passive"))
      (node (ref "R6") (pin "2") (pintype "passive"))
      (node (ref "U2") (pin "3") (pinfunction "FB_3") (pintype "passive"))
    )
    (net (code "63") (name "Net-(U2-SW)") (class "Default")
      (node (ref "D2") (pin "1") (pintype "passive"))
      (node (ref "L3") (pin "2") (pintype "passive"))
      (node (ref "U2") (pin "1") (pinfunction "SW_1") (pintype "power_in"))
    )
    (net (code "64") (name "Net-(U3-IN+)") (class "Default")
      (node (ref "C9") (pin "2") (pintype "passive"))
      (node (ref "R3") (pin "1") (pintype "passive"))
      (node (ref "U3") (pin "3") (pinfunction "IN+_3") (pintype "passive"))
    )
    (net (code "65") (name "Net-(U3-IN-)") (class "Default")
      (node (ref "C9") (pin "1") (pintype "passive"))
      (node (ref "R10") (pin "1") (pintype "passive"))
      (node (ref "U3") (pin "4") (pinfunction "IN-_4") (pintype "passive"))
    )
    (net (code "66") (name "Net-(U4-FB)") (class "Default")
      (node (ref "R13") (pin "1") (pintype "passive"))
      (node (ref "R15") (pin "2") (pintype "passive"))
      (node (ref "R16") (pin "1") (pintype "passive"))
      (node (ref "U4") (pin "6") (pinfunction "FB_6") (pintype "passive"))
    )
    (net (code "67") (name "Net-(U4-LX)") (class "Default")
      (node (ref "D7") (pin "1") (pintype "passive"))
      (node (ref "D8") (pin "1") (pintype "passive"))
      (node (ref "L5") (pin "2") (pintype "passive"))
      (node (ref "U4") (pin "8") (pinfunction "LX_8") (pintype "power_in"))
    )
    (net (code "68") (name "Net-(U4-OC)") (class "Default")
      (node (ref "R14") (pin "2") (pintype "passive"))
      (node (ref "U4") (pin "2") (pinfunction "OC_2") (pintype "passive"))
    )
    (net (code "69") (name "VCC") (class "Default")
      (node (ref "C18") (pin "2") (pintype "passive"))
      (node (ref "C19") (pin "2") (pintype "passive"))
      (node (ref "C20") (pin "2") (pintype "passive"))
      (node (ref "C21") (pin "2") (pintype "passive"))
      (node (ref "L6") (pin "1") (pintype "passive"))
      (node (ref "R12") (pin "1") (pintype "passive"))
      (node (ref "R20") (pin "2") (pintype "passive"))
      (node (ref "R21") (pin "2") (pintype "passive"))
      (node (ref "R22") (pin "2") (pintype "passive"))
      (node (ref "R27") (pin "2") (pintype "passive"))
      (node (ref "U1") (pin "24") (pinfunction "VDD_1_24") (pintype "power_in"))
      (node (ref "U1") (pin "36") (pinfunction "VDD_2_36") (pintype "power_in"))
      (node (ref "U1") (pin "48") (pinfunction "VDD_3_48") (pintype "power_in"))
      (node (ref "U3") (pin "5") (pinfunction "VCC_5") (pintype "passive"))
      (node (ref "U5") (pin "2") (pinfunction "Out_2") (pintype "passive"))
    )
    (net (code "70") (name "aGND") (class "Default")
      (node (ref "C13") (pin "1") (pintype "passive"))
      (node (ref "C14") (pin "1") (pintype "passive"))
      (node (ref "C15") (pin "1") (pintype "passive"))
      (node (ref "C16") (pin "1") (pintype "passive"))
      (node (ref "D3") (pin "1") (pintype "passive"))
      (node (ref "D6") (pin "1") (pintype "passive"))
      (node (ref "R14") (pin "1") (pintype "passive"))
      (node (ref "R15") (pin "1") (pintype "passive"))
      (node (ref "T1") (pin "3") (pinfunction "D_3") (pintype "passive"))
      (node (ref "T4") (pin "2") (pinfunction "S_2") (pintype "passive"))
      (node (ref "T5") (pin "2") (pinfunction "S_2") (pintype "passive"))
      (node (ref "U4") (pin "1") (pinfunction "PGND_1") (pintype "power_in"))
      (node (ref "U4") (pin "5") (pinfunction "GND_5") (pintype "power_in"))
      (node (ref "U4") (pin "9") (pinfunction "PAD_9") (pintype "passive"))
    )
    (net (code "71") (name "unconnected-(U1A-BOOT0-Pad44)") (class "Default")
      (node (ref "U1") (pin "44") (pinfunction "BOOT0_44") (pintype "input"))
    )
    (net (code "72") (name "unconnected-(U1A-PA3-Pad13)") (class "Default")
      (node (ref "U1") (pin "13") (pinfunction "PA3_13") (pintype "bidirectional"))
    )
    (net (code "73") (name "unconnected-(U1A-PA5-Pad15)") (class "Default")
      (node (ref "U1") (pin "15") (pinfunction "PA5_15") (pintype "bidirectional"))
    )
    (net (code "74") (name "unconnected-(U1A-PA15-Pad38)") (class "Default")
      (node (ref "U1") (pin "38") (pinfunction "PA15_38") (pintype "bidirectional"))
    )
    (net (code "75") (name "unconnected-(U1A-PB2-Pad20)") (class "Default")
      (node (ref "U1") (pin "20") (pinfunction "PB2_20") (pintype "bidirectional"))
    )
    (net (code "76") (name "unconnected-(U1A-PB3-Pad39)") (class "Default")
      (node (ref "U1") (pin "39") (pinfunction "PB3_39") (pintype "bidirectional"))
    )
    (net (code "77") (name "unconnected-(U1A-PB4-Pad40)") (class "Default")
      (node (ref "U1") (pin "40") (pinfunction "PB4_40") (pintype "bidirectional"))
    )
    (net (code "78") (name "unconnected-(U1A-PB5-Pad41)") (class "Default")
      (node (ref "U1") (pin "41") (pinfunction "PB5_41") (pintype "bidirectional"))
    )
    (net (code "79") (name "unconnected-(U1A-PB6-Pad42)") (class "Default")
      (node (ref "U1") (pin "42") (pinfunction "PB6_42") (pintype "bidirectional"))
    )
    (net (code "80") (name "unconnected-(U1A-PB8-Pad45)") (class "Default")
      (node (ref "U1") (pin "45") (pinfunction "PB8_45") (pintype "bidirectional"))
    )
    (net (code "81") (name "unconnected-(U1A-PB10-Pad21)") (class "Default")
      (node (ref "U1") (pin "21") (pinfunction "PB10_21") (pintype "bidirectional"))
    )
    (net (code "82") (name "unconnected-(U1A-PB11-Pad22)") (class "Default")
      (node (ref "U1") (pin "22") (pinfunction "PB11_22") (pintype "bidirectional"))
    )
    (net (code "83") (name "unconnected-(U1A-PB12-Pad25)") (class "Default")
      (node (ref "U1") (pin "25") (pinfunction "PB12_25") (pintype "bidirectional"))
    )
    (net (code "84") (name "unconnected-(U1A-PB13-Pad26)") (class "Default")
      (node (ref "U1") (pin "26") (pinfunction "PB13_26") (pintype "bidirectional"))
    )
    (net (code "85") (name "unconnected-(U1A-PB14-Pad27)") (class "Default")
      (node (ref "U1") (pin "27") (pinfunction "PB14_27") (pintype "bidirectional"))
    )
    (net (code "86") (name "unconnected-(U1A-PC13-TAMPER-RTC-Pad2)") (class "Default")
      (node (ref "U1") (pin "2") (pinfunction "PC13-TAMPER-RTC_2") (pintype "bidirectional"))
    )
    (net (code "87") (name "unconnected-(U1A-PC14-OSC32_IN-Pad3)") (class "Default")
      (node (ref "U1") (pin "3") (pinfunction "PC14-OSC32_IN_3") (pintype "bidirectional"))
    )
    (net (code "88") (name "unconnected-(U1A-PC15-OSC32_OUT-Pad4)") (class "Default")
      (node (ref "U1") (pin "4") (pinfunction "PC15-OSC32_OUT_4") (pintype "bidirectional"))
    )
    (net (code "89") (name "unconnected-(U1B-VBAT-Pad1)") (class "Default")
      (node (ref "U1") (pin "1") (pinfunction "VBAT_1") (pintype "power_in"))
    )
    (net (code "90") (name "unconnected-(U4-NC-Pad7)") (class "Default")
      (node (ref "U4") (pin "7") (pinfunction "NC_7") (pintype "passive"))
    )
  )
)
